# Sheet1.net
KiCad netlist of a schematic drawn in Altium Designer
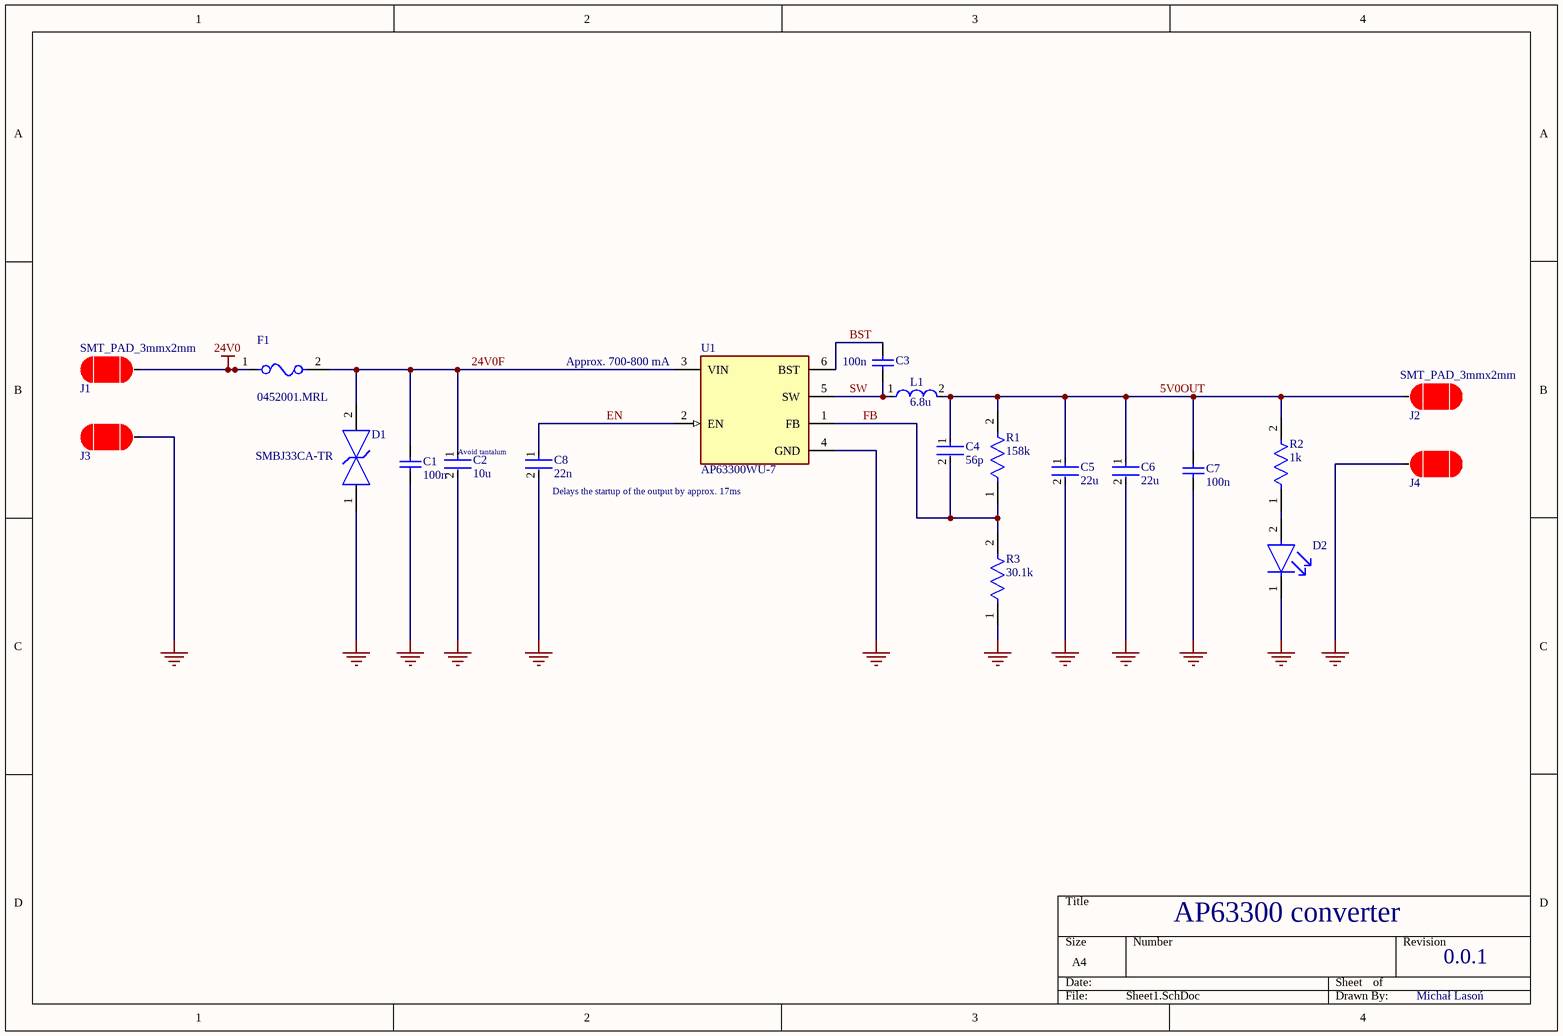
[diagram p0: Sheet1.SchDoc]

(export (version "E")
  (design (tool "Eeschema 10.0.6"))
  (components
    (comp (ref "C1")
      (value "100n")
      (footprint "CAPC2013X140X50NL20T25")
      (fields
        (field (name "PART NUMBER") "08055C104K4Z2A")
        (field (name "MANUFACTURER") "AVX Interconnect / Elco")
      )
      (libsource (lib "Altium Content Vault") (part "CAP"))
    )
    (comp (ref "C2")
      (value "10u")
      (footprint "FP-C3225-250-0_4-IPC_B")
      (description "Multilayer Ceramic Capacitors 10uF ±10% 50V X5R SMD 1210")
      (fields (field (name "TOLERANCE") "10%"))
      (libsource (lib "Altium Content Vault") (part "02cd4be3c70576c341d710602a673aa"))
    )
    (comp (ref "C3")
      (value "100n")
      (footprint "CAPC2013X140X50NL20T25")
      (fields
        (field (name "PART NUMBER") "08055C104K4Z2A")
        (field (name "MANUFACTURER") "AVX Interconnect / Elco")
      )
      (libsource (lib "Altium Content Vault") (part "CAP"))
    )
    (comp (ref "C4")
      (value "56p")
      (footprint "FP-C0805C-DN-MFG")
      (description "CAP CER 56PF 50V C0G/NP0 0805")
      (fields
        (field (name "TOLERANCE") "0.05")
        (field (name "OCTOPART") "https://octopart.com/c0805c560j5gactu-kemet-93783")
      )
      (libsource (lib "Altium Content Vault") (part "b4654b650e69147ec39a6b967a45e02"))
    )
    (comp (ref "C5")
      (value "22u")
      (footprint "FP-1210-L_3_3_0_4-W_2_5_0-IPC_A")
      (description "General Purpose Ceramic Capacitor, 1210, 22uF, 20%, X5R, 15%, 25V")
      (fields (field (name "VOLTAGE") "25V") (field (name "TOLERANCE") "20%"))
      (libsource (lib "Altium Content Vault") (part "b4654b650e69147ec39a6b967a45e02"))
    )
    (comp (ref "C6")
      (value "22u")
      (footprint "FP-1210-L_3_3_0_4-W_2_5_0-IPC_A")
      (description "General Purpose Ceramic Capacitor, 1210, 22uF, 20%, X5R, 15%, 25V")
      (fields (field (name "VOLTAGE") "25V") (field (name "TOLERANCE") "20%"))
      (libsource (lib "Altium Content Vault") (part "b4654b650e69147ec39a6b967a45e02"))
    )
    (comp (ref "C7")
      (value "100n")
      (footprint "CAPC2013X140X50NL20T25")
      (fields
        (field (name "PART NUMBER") "08055C104K4Z2A")
        (field (name "MANUFACTURER") "AVX Interconnect / Elco")
      )
      (libsource (lib "Altium Content Vault") (part "CAP"))
    )
    (comp (ref "C8")
      (value "22n")
      (footprint "FP-C0805C-DN-MFG")
      (description "CAP CER 0.022UF 50V X7R 0805")
      (fields
        (field (name "MANUFACTURER") "KEMET")
        (field (name "MANUFACTURER PART NUMBER") "C0805C223K5RACTU")
      )
      (libsource (lib "Altium Content Vault") (part "b4654b650e69147ec39a6b967a45e02"))
    )
    (comp (ref "D1")
      (value "SMBJ33CA-TR")
      (footprint "FP-SMB-CA-MFG")
      (description "TVS DIODE 33V 69.7V SMB")
      (fields
        (field (name "OCTOPART") "https://octopart.com/smbj33ca-tr-stmicroelectronics-347069")
        (field (name "MANUFACTURER") "STMicroelectronics")
      )
      (libsource (lib "Altium Content Vault") (part "11bd9d59d340f0612179daf16ad9b72"))
    )
    (comp (ref "D2")
      (value "HSMS-C170")
      (footprint "FP-HSMS-C170-MFG")
      (description "LED RED DIFFUSED CHIP SMD")
      (libsource (lib "Altium Content Vault") (part "8706943c75ba83719d021d2fdc84c58"))
    )
    (comp (ref "F1")
      (value "0452001.MRL")
      (footprint "FP-0452-MFG")
      (description "FUSE BRD MNT 1A 125VAC/VDC 2SMD")
      (fields
        (field (name "MANUFACTURER") "Littelfuse Inc")
        (field (name "OCTOPART") "https://octopart.com/0452001.mrl-littelfuse-566112")
      )
      (libsource (lib "Altium Content Vault") (part "5bcf9b9f640e542cf0359d10258e979"))
    )
    (comp (ref "J1")
      (value "SMT_PAD_3mmx2mm")
      (footprint "SMT_PAD_3mmx2mm")
      (libsource (lib "") (part "SMT_PAD_3mmx2mm_1"))
    )
    (comp (ref "J2")
      (value "SMT_PAD_3mmx2mm")
      (footprint "SMT_PAD_3mmx2mm")
      (libsource (lib "Schlib1") (part "SMT_PAD_3mmx2mm"))
    )
    (comp (ref "J3")
      (value "SMT_PAD_3mmx2mm")
      (footprint "SMT_PAD_3mmx2mm")
      (libsource (lib "") (part "SMT_PAD_3mmx2mm_1"))
    )
    (comp (ref "J4")
      (value "SMT_PAD_3mmx2mm")
      (footprint "SMT_PAD_3mmx2mm")
      (libsource (lib "Schlib1") (part "SMT_PAD_3mmx2mm"))
    )
    (comp (ref "L1")
      (value "6.8u")
      (footprint "FP-IHLP-2525CZ-FP_2_413x3-MFG")
      (description "Commercial Inductors, High Saturation Series 6.8uH 4.5A 60mΩ 20%")
      (fields (field (name "TOLERANCE") "20%"))
      (libsource (lib "Altium Content Vault") (part "725321dda6339637d4d059423bc1c3c"))
    )
    (comp (ref "R1")
      (value "158k")
      (footprint "FP-CRCW0805-e3-MFG")
      (description "RES Thick Film, 158kΩ, 1%, 0.125W, 100ppm/°C, 0805")
      (fields (field (name "TOLERANCE") "1%"))
      (libsource (lib "Altium Content Vault") (part "1029c3af85768c4190bb7ad29bc67b5"))
    )
    (comp (ref "R2")
      (value "1k")
      (footprint "FP-CR0805-IPC_B")
      (description "Thick Film Chip Resistors 0805 1kΩ 0.125W 1% 100ppm/°C")
      (fields (field (name "TOLERANCE") "1%"))
      (libsource (lib "Altium Content Vault") (part "1029c3af85768c4190bb7ad29bc67b5"))
    )
    (comp (ref "R3")
      (value "30.1k")
      (footprint "FP-CRCW0805-e3-IPC_C")
      (description "RES Thick Film, 30.1kΩ, 1%, 0.125W, 100ppm/°C, 0805")
      (fields (field (name "TOLERANCE") "1%"))
      (libsource (lib "Altium Content Vault") (part "1029c3af85768c4190bb7ad29bc67b5"))
    )
    (comp (ref "U1")
      (value "AP63300WU-7")
      (footprint "FP-TSOT26-IPC_A")
      (description "DCDC CONV HV BUCK TSOT26")
      (libsource (lib "Altium Content Vault") (part "1f55634e5cdcb17378ea3938d0fe863"))
    )
  )
  (nets
    (net (code "1") (name "/5V0OUT") (class "Default")
      (node (ref "C4") (pin "1") (pinfunction "1_1") (pintype "passive"))
      (node (ref "C5") (pin "1") (pinfunction "1_1") (pintype "passive"))
      (node (ref "C6") (pin "1") (pinfunction "1_1") (pintype "passive"))
      (node (ref "C7") (pin "2") (pinfunction "2_2") (pintype "passive"))
      (node (ref "J2") (pin "0") (pintype "passive"))
      (node (ref "L1") (pin "2") (pinfunction "2_2") (pintype "passive"))
      (node (ref "R1") (pin "2") (pinfunction "2_2") (pintype "passive"))
      (node (ref "R2") (pin "2") (pinfunction "2_2") (pintype "passive"))
    )
    (net (code "2") (name "/24V0F") (class "Default")
      (node (ref "C1") (pin "2") (pinfunction "2_2") (pintype "passive"))
      (node (ref "C2") (pin "1") (pinfunction "1_1") (pintype "passive"))
      (node (ref "D1") (pin "2") (pinfunction "2_2") (pintype "passive"))
      (node (ref "F1") (pin "2") (pinfunction "2_2") (pintype "passive"))
      (node (ref "U1") (pin "3") (pinfunction "VIN_3") (pintype "power_in"))
    )
    (net (code "3") (name "/BST") (class "Default")
      (node (ref "C3") (pin "2") (pinfunction "2_2") (pintype "passive"))
      (node (ref "U1") (pin "6") (pinfunction "BST_6") (pintype "passive"))
    )
    (net (code "4") (name "/EN") (class "Default")
      (node (ref "C8") (pin "1") (pinfunction "1_1") (pintype "passive"))
      (node (ref "U1") (pin "2") (pinfunction "EN_2") (pintype "input"))
    )
    (net (code "5") (name "/FB") (class "Default")
      (node (ref "C4") (pin "2") (pinfunction "2_2") (pintype "passive"))
      (node (ref "R1") (pin "1") (pinfunction "1_1") (pintype "passive"))
      (node (ref "R3") (pin "2") (pinfunction "2_2") (pintype "passive"))
      (node (ref "U1") (pin "1") (pinfunction "FB_1") (pintype "passive"))
    )
    (net (code "6") (name "/SW") (class "Default")
      (node (ref "C3") (pin "1") (pinfunction "1_1") (pintype "passive"))
      (node (ref "L1") (pin "1") (pinfunction "1_1") (pintype "passive"))
      (node (ref "U1") (pin "5") (pinfunction "SW_5") (pintype "passive"))
    )
    (net (code "7") (name "24V0") (class "Default")
      (node (ref "F1") (pin "1") (pinfunction "1_1") (pintype "passive"))
      (node (ref "J1") (pin "0") (pintype "passive"))
    )
    (net (code "8") (name "GND") (class "Default")
      (node (ref "C1") (pin "1") (pinfunction "1_1") (pintype "passive"))
      (node (ref "C2") (pin "2") (pinfunction "2_2") (pintype "passive"))
      (node (ref "C5") (pin "2") (pinfunction "2_2") (pintype "passive"))
      (node (ref "C6") (pin "2") (pinfunction "2_2") (pintype "passive"))
      (node (ref "C7") (pin "1") (pinfunction "1_1") (pintype "passive"))
      (node (ref "C8") (pin "2") (pinfunction "2_2") (pintype "passive"))
      (node (ref "D1") (pin "1") (pinfunction "1_1") (pintype "passive"))
      (node (ref "D2") (pin "1") (pinfunction "C_1") (pintype "passive"))
      (node (ref "J3") (pin "0") (pintype "passive"))
      (node (ref "J4") (pin "0") (pintype "passive"))
      (node (ref "R3") (pin "1") (pinfunction "1_1") (pintype "passive"))
      (node (ref "U1") (pin "4") (pinfunction "GND_4") (pintype "power_in"))
    )
    (net (code "9") (name "Net-(D2-A)") (class "Default")
      (node (ref "D2") (pin "2") (pinfunction "A_2") (pintype "passive"))
      (node (ref "R2") (pin "1") (pinfunction "1_1") (pintype "passive"))
    )
  )
)
